# PROC099B_HD_Connector.net
KiCad netlist of a schematic drawn in Altium Designer
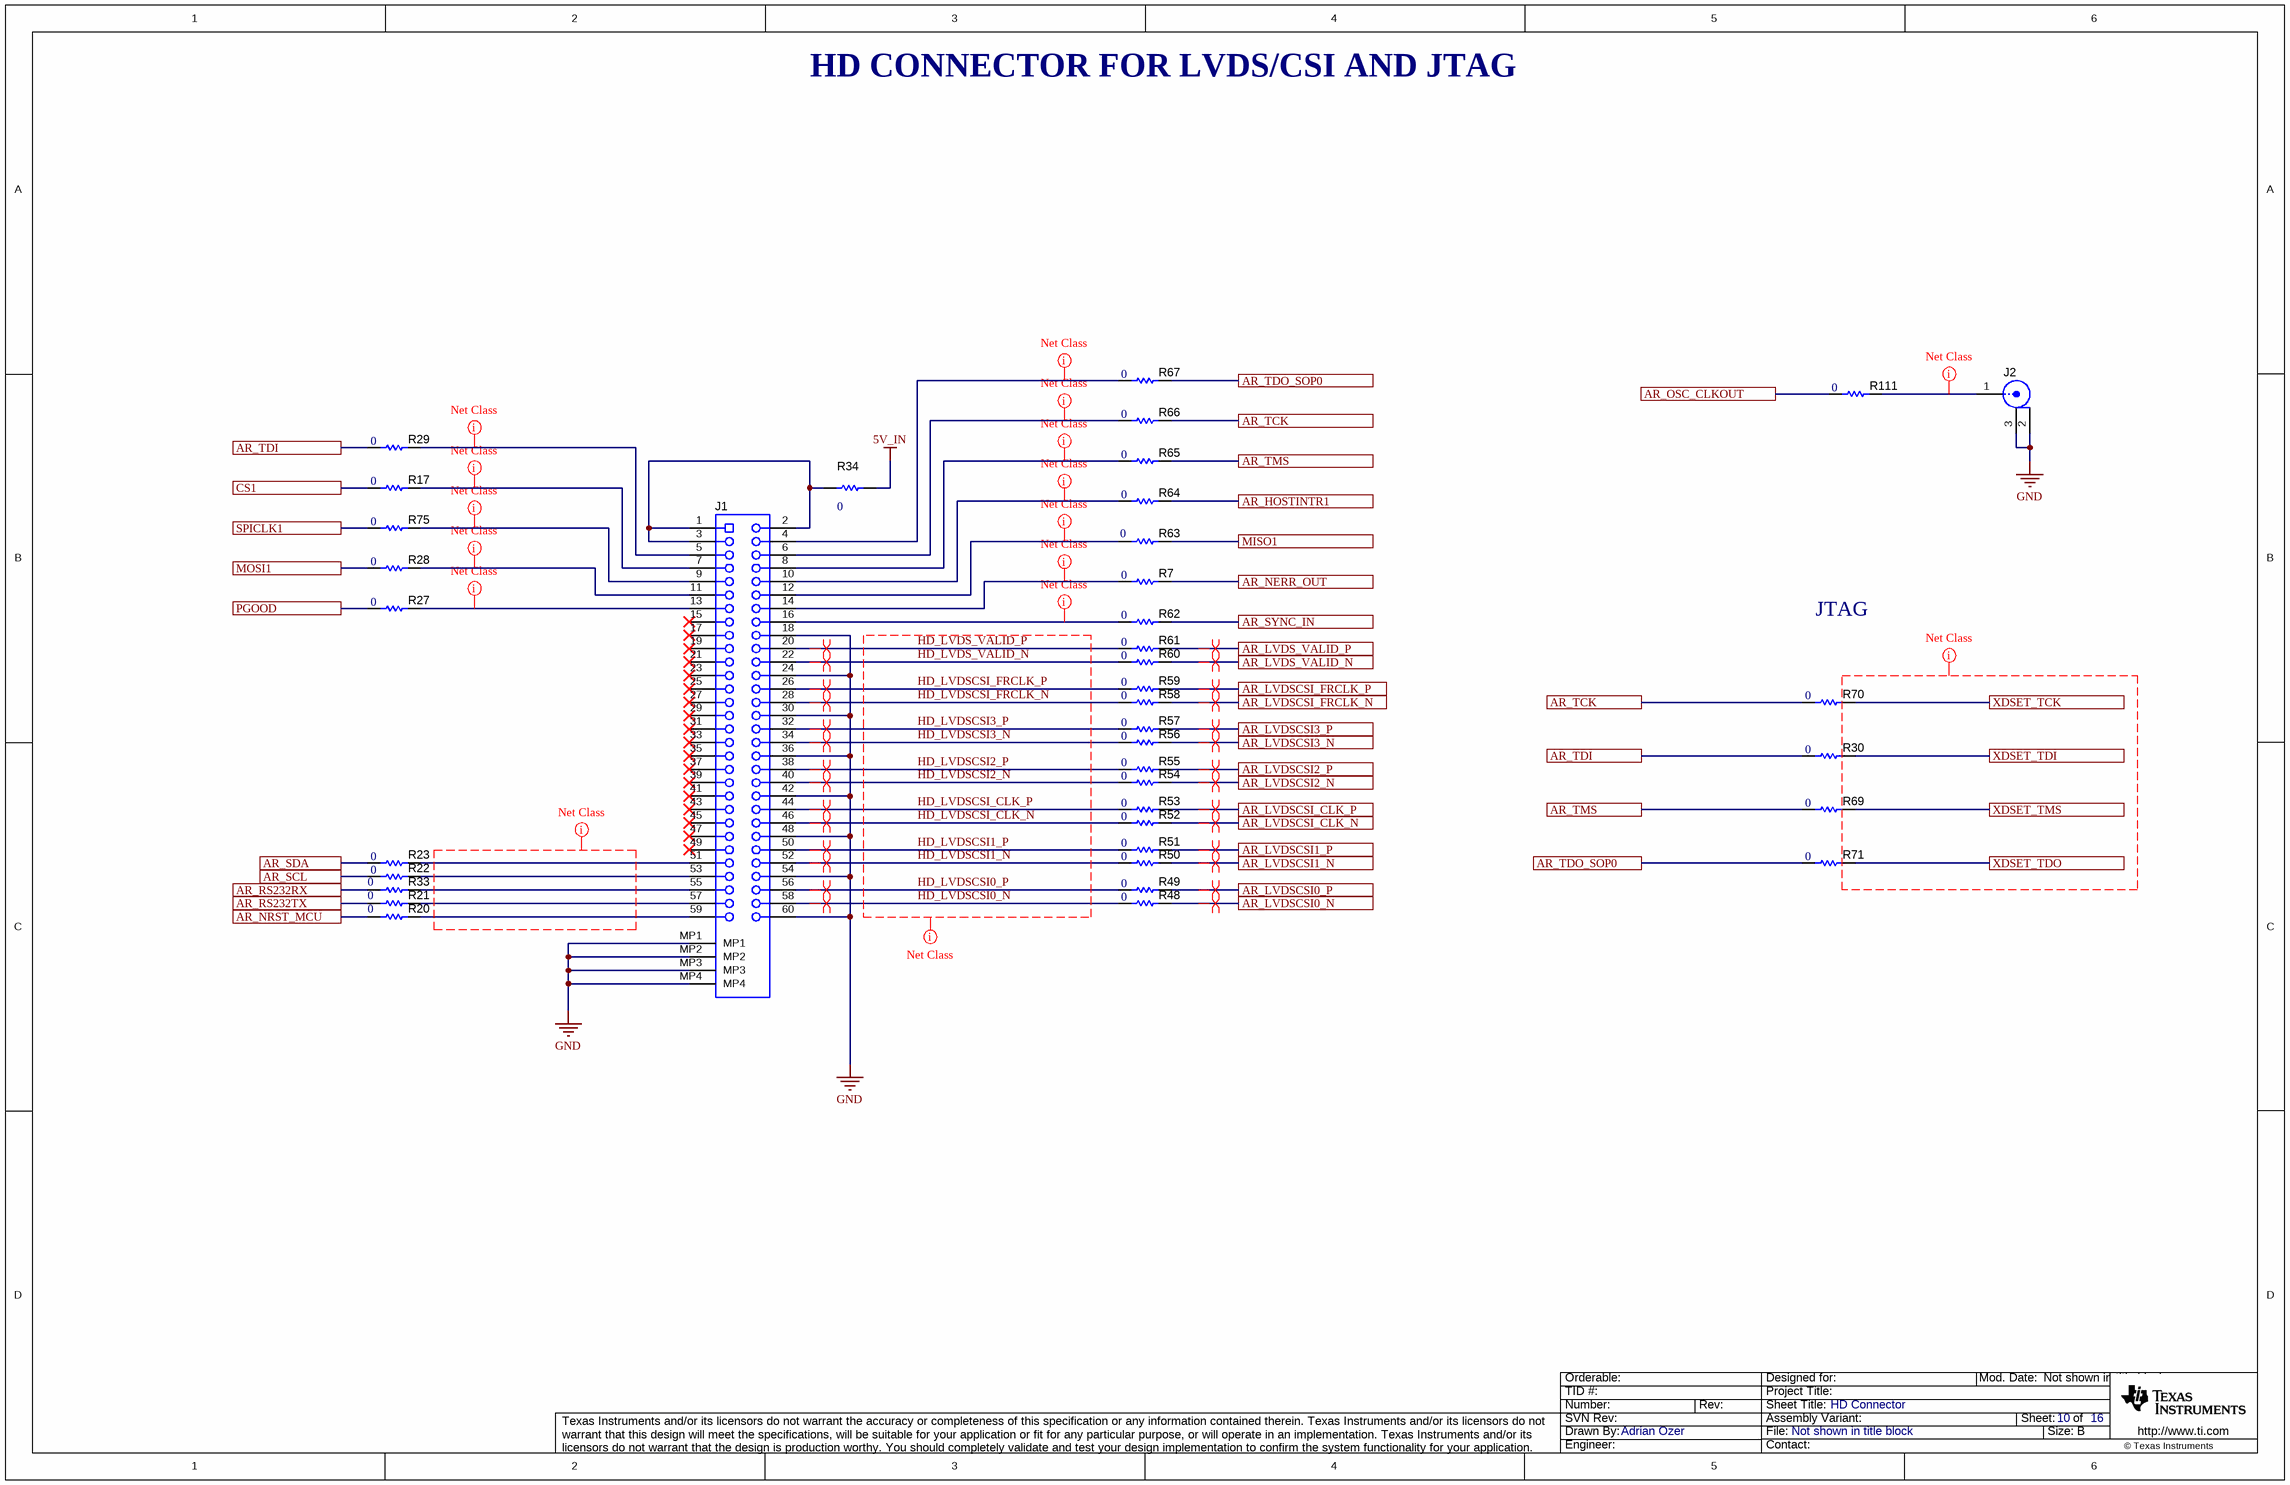
[diagram p0: PROC099B_HD Connector.SchDoc]

(export (version "E")
  (design (tool "Eeschema 10.0.6"))
  (components
    (comp (ref "J1")
      (value "QSH-030-01-L-D-A")
      (footprint "Samtec_QSH-030-01-X-D-A")
      (description "Receptacle, 0.5 mm, 30x2, Gold, TH")
      (fields (field (name "MANUFACTURER") "Samtec") (field (name "PUBLISHER") "Texas Instruments"))
      (libsource (lib "Altium Vault - TI") (part "Receptacle_30x2_4MP_LeftRight"))
    )
    (comp (ref "J2")
      (value "128-0711-201")
      (footprint "Johnson_128-0711-201")
      (description "UMC Straight Jack Receptacle, 50 Ohm, Gold, SMT")
      (fields
        (field (name "MANUFACTURER") "Cinch Connectivity")
        (field (name "PUBLISHER") "Texas Instruments")
      )
      (libsource (lib "Altium Vault - TI") (part "CMP-0055788-1"))
    )
    (comp (ref "R7")
      (value "CRCW02010000Z0ED")
      (footprint "0201_Silk")
      (description "RES, 0, 5%, 0.05 W, 0201")
      (fields (field (name "MANUFACTURER") "Vishay-Dale") (field (name "VALUEDISPLAYED") "0"))
      (libsource (lib "Altium Vault - TI") (part "Resistor"))
    )
    (comp (ref "R17")
      (value "CRCW02010000Z0ED")
      (footprint "0201_Silk")
      (description "RES, 0, 5%, 0.05 W, 0201")
      (fields (field (name "MANUFACTURER") "Vishay-Dale") (field (name "VALUEDISPLAYED") "0"))
      (libsource (lib "Altium Vault - TI") (part "Resistor"))
    )
    (comp (ref "R20")
      (value "CRCW02010000Z0ED")
      (footprint "0201_Silk")
      (description "RES, 0, 5%, 0.05 W, 0201")
      (fields (field (name "MANUFACTURER") "Vishay-Dale") (field (name "VALUEDISPLAYED") "0"))
      (libsource (lib "Altium Vault - TI") (part "Resistor"))
    )
    (comp (ref "R21")
      (value "CRCW02010000Z0ED")
      (footprint "0201_Silk")
      (description "RES, 0, 5%, 0.05 W, 0201")
      (fields (field (name "MANUFACTURER") "Vishay-Dale") (field (name "VALUEDISPLAYED") "0"))
      (libsource (lib "Altium Vault - TI") (part "Resistor"))
    )
    (comp (ref "R22")
      (value "CRCW02010000Z0ED")
      (footprint "0201_Silk")
      (description "RES, 0, 5%, 0.05 W, 0201")
      (fields (field (name "MANUFACTURER") "Vishay-Dale") (field (name "VALUEDISPLAYED") "0"))
      (libsource (lib "Altium Vault - TI") (part "Resistor"))
    )
    (comp (ref "R23")
      (value "CRCW02010000Z0ED")
      (footprint "0201_Silk")
      (description "RES, 0, 5%, 0.05 W, 0201")
      (fields (field (name "MANUFACTURER") "Vishay-Dale") (field (name "VALUEDISPLAYED") "0"))
      (libsource (lib "Altium Vault - TI") (part "Resistor"))
    )
    (comp (ref "R27")
      (value "CRCW02010000Z0ED")
      (footprint "0201_Silk")
      (description "RES, 0, 5%, 0.05 W, 0201")
      (fields (field (name "MANUFACTURER") "Vishay-Dale") (field (name "VALUEDISPLAYED") "0"))
      (libsource (lib "Altium Vault - TI") (part "Resistor"))
    )
    (comp (ref "R28")
      (value "CRCW02010000Z0ED")
      (footprint "0201_Silk")
      (description "RES, 0, 5%, 0.05 W, 0201")
      (fields (field (name "MANUFACTURER") "Vishay-Dale") (field (name "VALUEDISPLAYED") "0"))
      (libsource (lib "Altium Vault - TI") (part "Resistor"))
    )
    (comp (ref "R29")
      (value "CRCW02010000Z0ED")
      (footprint "0201_Silk")
      (description "RES, 0, 5%, 0.05 W, 0201")
      (fields (field (name "MANUFACTURER") "Vishay-Dale") (field (name "VALUEDISPLAYED") "0"))
      (libsource (lib "Altium Vault - TI") (part "Resistor"))
    )
    (comp (ref "R30")
      (value "CRCW02010000Z0ED")
      (footprint "0201_Silk")
      (description "RES, 0, 5%, 0.05 W, 0201")
      (fields (field (name "MANUFACTURER") "Vishay-Dale") (field (name "VALUEDISPLAYED") "0"))
      (libsource (lib "Altium Vault - TI") (part "Resistor"))
    )
    (comp (ref "R33")
      (value "CRCW02010000Z0ED")
      (footprint "0201_Silk")
      (description "RES, 0, 5%, 0.05 W, 0201")
      (fields (field (name "MANUFACTURER") "Vishay-Dale") (field (name "VALUEDISPLAYED") "0"))
      (libsource (lib "Altium Vault - TI") (part "Resistor"))
    )
    (comp (ref "R34")
      (value "CRCW20100000Z0EF")
      (footprint "2010L")
      (description "RES, 0, 5%, 0.75 W, AEC-Q200 Grade 0, 2010")
      (fields (field (name "MANUFACTURER") "Vishay-Dale") (field (name "VALUEDISPLAYED") "0"))
      (libsource (lib "Altium Vault - TI") (part "CMP-0016044-3"))
    )
    (comp (ref "R48")
      (value "CRCW02010000Z0ED")
      (footprint "0201_Silk")
      (description "RES, 0, 5%, 0.05 W, 0201")
      (fields (field (name "MANUFACTURER") "Vishay-Dale") (field (name "VALUEDISPLAYED") "0"))
      (libsource (lib "Altium Vault - TI") (part "Resistor"))
    )
    (comp (ref "R49")
      (value "CRCW02010000Z0ED")
      (footprint "0201_Silk")
      (description "RES, 0, 5%, 0.05 W, 0201")
      (fields (field (name "MANUFACTURER") "Vishay-Dale") (field (name "VALUEDISPLAYED") "0"))
      (libsource (lib "Altium Vault - TI") (part "Resistor"))
    )
    (comp (ref "R50")
      (value "CRCW02010000Z0ED")
      (footprint "0201_Silk")
      (description "RES, 0, 5%, 0.05 W, 0201")
      (fields (field (name "MANUFACTURER") "Vishay-Dale") (field (name "VALUEDISPLAYED") "0"))
      (libsource (lib "Altium Vault - TI") (part "Resistor"))
    )
    (comp (ref "R51")
      (value "CRCW02010000Z0ED")
      (footprint "0201_Silk")
      (description "RES, 0, 5%, 0.05 W, 0201")
      (fields (field (name "MANUFACTURER") "Vishay-Dale") (field (name "VALUEDISPLAYED") "0"))
      (libsource (lib "Altium Vault - TI") (part "Resistor"))
    )
    (comp (ref "R52")
      (value "CRCW02010000Z0ED")
      (footprint "0201_Silk")
      (description "RES, 0, 5%, 0.05 W, 0201")
      (fields (field (name "MANUFACTURER") "Vishay-Dale") (field (name "VALUEDISPLAYED") "0"))
      (libsource (lib "Altium Vault - TI") (part "Resistor"))
    )
    (comp (ref "R53")
      (value "CRCW02010000Z0ED")
      (footprint "0201_Silk")
      (description "RES, 0, 5%, 0.05 W, 0201")
      (fields (field (name "MANUFACTURER") "Vishay-Dale") (field (name "VALUEDISPLAYED") "0"))
      (libsource (lib "Altium Vault - TI") (part "Resistor"))
    )
    (comp (ref "R54")
      (value "CRCW02010000Z0ED")
      (footprint "0201_Silk")
      (description "RES, 0, 5%, 0.05 W, 0201")
      (fields (field (name "MANUFACTURER") "Vishay-Dale") (field (name "VALUEDISPLAYED") "0"))
      (libsource (lib "Altium Vault - TI") (part "Resistor"))
    )
    (comp (ref "R55")
      (value "CRCW02010000Z0ED")
      (footprint "0201_Silk")
      (description "RES, 0, 5%, 0.05 W, 0201")
      (fields (field (name "MANUFACTURER") "Vishay-Dale") (field (name "VALUEDISPLAYED") "0"))
      (libsource (lib "Altium Vault - TI") (part "Resistor"))
    )
    (comp (ref "R56")
      (value "CRCW02010000Z0ED")
      (footprint "0201_Silk")
      (description "RES, 0, 5%, 0.05 W, 0201")
      (fields (field (name "MANUFACTURER") "Vishay-Dale") (field (name "VALUEDISPLAYED") "0"))
      (libsource (lib "Altium Vault - TI") (part "Resistor"))
    )
    (comp (ref "R57")
      (value "CRCW02010000Z0ED")
      (footprint "0201_Silk")
      (description "RES, 0, 5%, 0.05 W, 0201")
      (fields (field (name "MANUFACTURER") "Vishay-Dale") (field (name "VALUEDISPLAYED") "0"))
      (libsource (lib "Altium Vault - TI") (part "Resistor"))
    )
    (comp (ref "R58")
      (value "CRCW02010000Z0ED")
      (footprint "0201_Silk")
      (description "RES, 0, 5%, 0.05 W, 0201")
      (fields (field (name "MANUFACTURER") "Vishay-Dale") (field (name "VALUEDISPLAYED") "0"))
      (libsource (lib "Altium Vault - TI") (part "Resistor"))
    )
    (comp (ref "R59")
      (value "CRCW02010000Z0ED")
      (footprint "0201_Silk")
      (description "RES, 0, 5%, 0.05 W, 0201")
      (fields (field (name "MANUFACTURER") "Vishay-Dale") (field (name "VALUEDISPLAYED") "0"))
      (libsource (lib "Altium Vault - TI") (part "Resistor"))
    )
    (comp (ref "R60")
      (value "CRCW02010000Z0ED")
      (footprint "0201_Silk")
      (description "RES, 0, 5%, 0.05 W, 0201")
      (fields (field (name "MANUFACTURER") "Vishay-Dale") (field (name "VALUEDISPLAYED") "0"))
      (libsource (lib "Altium Vault - TI") (part "Resistor"))
    )
    (comp (ref "R61")
      (value "CRCW02010000Z0ED")
      (footprint "0201_Silk")
      (description "RES, 0, 5%, 0.05 W, 0201")
      (fields (field (name "MANUFACTURER") "Vishay-Dale") (field (name "VALUEDISPLAYED") "0"))
      (libsource (lib "Altium Vault - TI") (part "Resistor"))
    )
    (comp (ref "R62")
      (value "CRCW02010000Z0ED")
      (footprint "0201_Silk")
      (description "RES, 0, 5%, 0.05 W, 0201")
      (fields (field (name "MANUFACTURER") "Vishay-Dale") (field (name "VALUEDISPLAYED") "0"))
      (libsource (lib "Altium Vault - TI") (part "Resistor"))
    )
    (comp (ref "R63")
      (value "CRCW02010000Z0ED")
      (footprint "0201_Silk")
      (description "RES, 0, 5%, 0.05 W, 0201")
      (fields (field (name "MANUFACTURER") "Vishay-Dale") (field (name "VALUEDISPLAYED") "0"))
      (libsource (lib "Altium Vault - TI") (part "Resistor"))
    )
    (comp (ref "R64")
      (value "CRCW02010000Z0ED")
      (footprint "0201_Silk")
      (description "RES, 0, 5%, 0.05 W, 0201")
      (fields (field (name "MANUFACTURER") "Vishay-Dale") (field (name "VALUEDISPLAYED") "0"))
      (libsource (lib "Altium Vault - TI") (part "Resistor"))
    )
    (comp (ref "R65")
      (value "CRCW02010000Z0ED")
      (footprint "0201_Silk")
      (description "RES, 0, 5%, 0.05 W, 0201")
      (fields (field (name "MANUFACTURER") "Vishay-Dale") (field (name "VALUEDISPLAYED") "0"))
      (libsource (lib "Altium Vault - TI") (part "Resistor"))
    )
    (comp (ref "R66")
      (value "CRCW02010000Z0ED")
      (footprint "0201_Silk")
      (description "RES, 0, 5%, 0.05 W, 0201")
      (fields (field (name "MANUFACTURER") "Vishay-Dale") (field (name "VALUEDISPLAYED") "0"))
      (libsource (lib "Altium Vault - TI") (part "Resistor"))
    )
    (comp (ref "R67")
      (value "CRCW02010000Z0ED")
      (footprint "0201_Silk")
      (description "RES, 0, 5%, 0.05 W, 0201")
      (fields (field (name "MANUFACTURER") "Vishay-Dale") (field (name "VALUEDISPLAYED") "0"))
      (libsource (lib "Altium Vault - TI") (part "Resistor"))
    )
    (comp (ref "R69")
      (value "CRCW02010000Z0ED")
      (footprint "0201_Silk")
      (description "RES, 0, 5%, 0.05 W, 0201")
      (fields (field (name "MANUFACTURER") "Vishay-Dale") (field (name "VALUEDISPLAYED") "0"))
      (libsource (lib "Altium Vault - TI") (part "Resistor"))
    )
    (comp (ref "R70")
      (value "CRCW02010000Z0ED")
      (footprint "0201_Silk")
      (description "RES, 0, 5%, 0.05 W, 0201")
      (fields (field (name "MANUFACTURER") "Vishay-Dale") (field (name "VALUEDISPLAYED") "0"))
      (libsource (lib "Altium Vault - TI") (part "Resistor"))
    )
    (comp (ref "R71")
      (value "CRCW02010000Z0ED")
      (footprint "0201_Silk")
      (description "RES, 0, 5%, 0.05 W, 0201")
      (fields (field (name "MANUFACTURER") "Vishay-Dale") (field (name "VALUEDISPLAYED") "0"))
      (libsource (lib "Altium Vault - TI") (part "Resistor"))
    )
    (comp (ref "R75")
      (value "CRCW02010000Z0ED")
      (footprint "0201_Silk")
      (description "RES, 0, 5%, 0.05 W, 0201")
      (fields (field (name "MANUFACTURER") "Vishay-Dale") (field (name "VALUEDISPLAYED") "0"))
      (libsource (lib "Altium Vault - TI") (part "Resistor"))
    )
    (comp (ref "R111")
      (value "CRCW02010000Z0ED")
      (footprint "0201_Silk")
      (description "RES, 0, 5%, 0.05 W, 0201")
      (fields (field (name "MANUFACTURER") "Vishay-Dale") (field (name "VALUEDISPLAYED") "0"))
      (libsource (lib "Altium Vault - TI") (part "Resistor"))
    )
  )
  (nets
    (net (code "1") (name "/AR_HOSTINTR1") (class "Default")
      (node (ref "R64") (pin "2") (pinfunction "2_2") (pintype "passive"))
    )
    (net (code "2") (name "/AR_LVDSCSI0_N") (class "Default")
      (node (ref "R48") (pin "2") (pinfunction "2_2") (pintype "passive"))
    )
    (net (code "3") (name "/AR_LVDSCSI0_P") (class "Default")
      (node (ref "R49") (pin "2") (pinfunction "2_2") (pintype "passive"))
    )
    (net (code "4") (name "/AR_LVDSCSI1_N") (class "Default")
      (node (ref "R50") (pin "2") (pinfunction "2_2") (pintype "passive"))
    )
    (net (code "5") (name "/AR_LVDSCSI1_P") (class "Default")
      (node (ref "R51") (pin "2") (pinfunction "2_2") (pintype "passive"))
    )
    (net (code "6") (name "/AR_LVDSCSI2_N") (class "Default")
      (node (ref "R54") (pin "2") (pinfunction "2_2") (pintype "passive"))
    )
    (net (code "7") (name "/AR_LVDSCSI2_P") (class "Default")
      (node (ref "R55") (pin "2") (pinfunction "2_2") (pintype "passive"))
    )
    (net (code "8") (name "/AR_LVDSCSI3_N") (class "Default")
      (node (ref "R56") (pin "2") (pinfunction "2_2") (pintype "passive"))
    )
    (net (code "9") (name "/AR_LVDSCSI3_P") (class "Default")
      (node (ref "R57") (pin "2") (pinfunction "2_2") (pintype "passive"))
    )
    (net (code "10") (name "/AR_LVDSCSI_CLK_N") (class "Default")
      (node (ref "R52") (pin "2") (pinfunction "2_2") (pintype "passive"))
    )
    (net (code "11") (name "/AR_LVDSCSI_CLK_P") (class "Default")
      (node (ref "R53") (pin "2") (pinfunction "2_2") (pintype "passive"))
    )
    (net (code "12") (name "/AR_LVDSCSI_FRCLK_N") (class "Default")
      (node (ref "R58") (pin "2") (pinfunction "2_2") (pintype "passive"))
    )
    (net (code "13") (name "/AR_LVDSCSI_FRCLK_P") (class "Default")
      (node (ref "R59") (pin "2") (pinfunction "2_2") (pintype "passive"))
    )
    (net (code "14") (name "/AR_LVDS_VALID_N") (class "Default")
      (node (ref "R60") (pin "2") (pinfunction "2_2") (pintype "passive"))
    )
    (net (code "15") (name "/AR_LVDS_VALID_P") (class "Default")
      (node (ref "R61") (pin "2") (pinfunction "2_2") (pintype "passive"))
    )
    (net (code "16") (name "/AR_NERR_OUT") (class "Default")
      (node (ref "R7") (pin "2") (pinfunction "2_2") (pintype "passive"))
    )
    (net (code "17") (name "/AR_NRST_MCU") (class "Default")
      (node (ref "R20") (pin "1") (pinfunction "1_1") (pintype "passive"))
    )
    (net (code "18") (name "/AR_OSC_CLKOUT") (class "Default")
      (node (ref "R111") (pin "1") (pinfunction "1_1") (pintype "passive"))
    )
    (net (code "19") (name "/AR_RS232RX") (class "Default")
      (node (ref "R33") (pin "1") (pinfunction "1_1") (pintype "passive"))
    )
    (net (code "20") (name "/AR_RS232TX") (class "Default")
      (node (ref "R21") (pin "1") (pinfunction "1_1") (pintype "passive"))
    )
    (net (code "21") (name "/AR_SCL") (class "Default")
      (node (ref "R22") (pin "1") (pinfunction "1_1") (pintype "passive"))
    )
    (net (code "22") (name "/AR_SDA") (class "Default")
      (node (ref "R23") (pin "1") (pinfunction "1_1") (pintype "passive"))
    )
    (net (code "23") (name "/AR_SYNC_IN") (class "Default")
      (node (ref "R62") (pin "2") (pinfunction "2_2") (pintype "passive"))
    )
    (net (code "24") (name "/AR_TCK") (class "Default")
      (node (ref "R66") (pin "2") (pinfunction "2_2") (pintype "passive"))
      (node (ref "R70") (pin "1") (pinfunction "1_1") (pintype "passive"))
    )
    (net (code "25") (name "/AR_TDI") (class "Default")
      (node (ref "R29") (pin "1") (pinfunction "1_1") (pintype "passive"))
      (node (ref "R30") (pin "1") (pinfunction "1_1") (pintype "passive"))
    )
    (net (code "26") (name "/AR_TDO_SOP0") (class "Default")
      (node (ref "R67") (pin "2") (pinfunction "2_2") (pintype "passive"))
      (node (ref "R71") (pin "1") (pinfunction "1_1") (pintype "passive"))
    )
    (net (code "27") (name "/AR_TMS") (class "Default")
      (node (ref "R65") (pin "2") (pinfunction "2_2") (pintype "passive"))
      (node (ref "R69") (pin "1") (pinfunction "1_1") (pintype "passive"))
    )
    (net (code "28") (name "/CS1") (class "Default")
      (node (ref "R17") (pin "1") (pinfunction "1_1") (pintype "passive"))
    )
    (net (code "29") (name "/HD_LVDSCSI0_N") (class "Default")
      (node (ref "J1") (pin "58") (pinfunction "58_58") (pintype "passive"))
      (node (ref "R48") (pin "1") (pinfunction "1_1") (pintype "passive"))
    )
    (net (code "30") (name "/HD_LVDSCSI0_P") (class "Default")
      (node (ref "J1") (pin "56") (pinfunction "56_56") (pintype "passive"))
      (node (ref "R49") (pin "1") (pinfunction "1_1") (pintype "passive"))
    )
    (net (code "31") (name "/HD_LVDSCSI1_N") (class "Default")
      (node (ref "J1") (pin "52") (pinfunction "52_52") (pintype "passive"))
      (node (ref "R50") (pin "1") (pinfunction "1_1") (pintype "passive"))
    )
    (net (code "32") (name "/HD_LVDSCSI1_P") (class "Default")
      (node (ref "J1") (pin "50") (pinfunction "50_50") (pintype "passive"))
      (node (ref "R51") (pin "1") (pinfunction "1_1") (pintype "passive"))
    )
    (net (code "33") (name "/HD_LVDSCSI2_N") (class "Default")
      (node (ref "J1") (pin "40") (pinfunction "40_40") (pintype "passive"))
      (node (ref "R54") (pin "1") (pinfunction "1_1") (pintype "passive"))
    )
    (net (code "34") (name "/HD_LVDSCSI2_P") (class "Default")
      (node (ref "J1") (pin "38") (pinfunction "38_38") (pintype "passive"))
      (node (ref "R55") (pin "1") (pinfunction "1_1") (pintype "passive"))
    )
    (net (code "35") (name "/HD_LVDSCSI3_N") (class "Default")
      (node (ref "J1") (pin "34") (pinfunction "34_34") (pintype "passive"))
      (node (ref "R56") (pin "1") (pinfunction "1_1") (pintype "passive"))
    )
    (net (code "36") (name "/HD_LVDSCSI3_P") (class "Default")
      (node (ref "J1") (pin "32") (pinfunction "32_32") (pintype "passive"))
      (node (ref "R57") (pin "1") (pinfunction "1_1") (pintype "passive"))
    )
    (net (code "37") (name "/HD_LVDSCSI_CLK_N") (class "Default")
      (node (ref "J1") (pin "46") (pinfunction "46_46") (pintype "passive"))
      (node (ref "R52") (pin "1") (pinfunction "1_1") (pintype "passive"))
    )
    (net (code "38") (name "/HD_LVDSCSI_CLK_P") (class "Default")
      (node (ref "J1") (pin "44") (pinfunction "44_44") (pintype "passive"))
      (node (ref "R53") (pin "1") (pinfunction "1_1") (pintype "passive"))
    )
    (net (code "39") (name "/HD_LVDSCSI_FRCLK_N") (class "Default")
      (node (ref "J1") (pin "28") (pinfunction "28_28") (pintype "passive"))
      (node (ref "R58") (pin "1") (pinfunction "1_1") (pintype "passive"))
    )
    (net (code "40") (name "/HD_LVDSCSI_FRCLK_P") (class "Default")
      (node (ref "J1") (pin "26") (pinfunction "26_26") (pintype "passive"))
      (node (ref "R59") (pin "1") (pinfunction "1_1") (pintype "passive"))
    )
    (net (code "41") (name "/HD_LVDS_VALID_N") (class "Default")
      (node (ref "J1") (pin "22") (pinfunction "22_22") (pintype "passive"))
      (node (ref "R60") (pin "1") (pinfunction "1_1") (pintype "passive"))
    )
    (net (code "42") (name "/HD_LVDS_VALID_P") (class "Default")
      (node (ref "J1") (pin "20") (pinfunction "20_20") (pintype "passive"))
      (node (ref "R61") (pin "1") (pinfunction "1_1") (pintype "passive"))
    )
    (net (code "43") (name "/MISO1") (class "Default")
      (node (ref "R63") (pin "2") (pinfunction "2_2") (pintype "passive"))
    )
    (net (code "44") (name "/MOSI1") (class "Default")
      (node (ref "R28") (pin "1") (pinfunction "1_1") (pintype "passive"))
    )
    (net (code "45") (name "/PGOOD") (class "Default")
      (node (ref "R27") (pin "1") (pinfunction "1_1") (pintype "passive"))
    )
    (net (code "46") (name "/SPICLK1") (class "Default")
      (node (ref "R75") (pin "1") (pinfunction "1_1") (pintype "passive"))
    )
    (net (code "47") (name "/XDSET_TCK") (class "Default")
      (node (ref "R70") (pin "2") (pinfunction "2_2") (pintype "passive"))
    )
    (net (code "48") (name "/XDSET_TDI") (class "Default")
      (node (ref "R30") (pin "2") (pinfunction "2_2") (pintype "passive"))
    )
    (net (code "49") (name "/XDSET_TDO") (class "Default")
      (node (ref "R71") (pin "2") (pinfunction "2_2") (pintype "passive"))
    )
    (net (code "50") (name "/XDSET_TMS") (class "Default")
      (node (ref "R69") (pin "2") (pinfunction "2_2") (pintype "passive"))
    )
    (net (code "51") (name "5V_IN") (class "Default")
      (node (ref "R34") (pin "2") (pinfunction "2_2") (pintype "passive"))
    )
    (net (code "52") (name "GND") (class "Default")
      (node (ref "J1") (pin "18") (pinfunction "18_18") (pintype "passive"))
      (node (ref "J1") (pin "24") (pinfunction "24_24") (pintype "passive"))
      (node (ref "J1") (pin "30") (pinfunction "30_30") (pintype "passive"))
      (node (ref "J1") (pin "36") (pinfunction "36_36") (pintype "passive"))
      (node (ref "J1") (pin "42") (pinfunction "42_42") (pintype "passive"))
      (node (ref "J1") (pin "48") (pinfunction "48_48") (pintype "passive"))
      (node (ref "J1") (pin "54") (pinfunction "54_54") (pintype "passive"))
      (node (ref "J1") (pin "60") (pinfunction "60_60") (pintype "passive"))
      (node (ref "J1") (pin "MP1") (pinfunction "MP1_MP1") (pintype "passive"))
      (node (ref "J1") (pin "MP2") (pinfunction "MP2_MP2") (pintype "passive"))
      (node (ref "J1") (pin "MP3") (pinfunction "MP3_MP3") (pintype "passive"))
      (node (ref "J1") (pin "MP4") (pinfunction "MP4_MP4") (pintype "passive"))
      (node (ref "J2") (pin "2") (pinfunction "2_2") (pintype "passive"))
      (node (ref "J2") (pin "3") (pinfunction "3_3") (pintype "passive"))
    )
    (net (code "53") (name "Net-(J1-Pad1)") (class "Default")
      (node (ref "J1") (pin "1") (pinfunction "1_1") (pintype "passive"))
      (node (ref "J1") (pin "2") (pinfunction "2_2") (pintype "passive"))
      (node (ref "J1") (pin "3") (pinfunction "3_3") (pintype "passive"))
      (node (ref "R34") (pin "1") (pinfunction "1_1") (pintype "passive"))
    )
    (net (code "54") (name "Net-(J1-Pad4)") (class "Default")
      (node (ref "J1") (pin "4") (pinfunction "4_4") (pintype "passive"))
      (node (ref "R67") (pin "1") (pinfunction "1_1") (pintype "passive"))
    )
    (net (code "55") (name "Net-(J1-Pad5)") (class "Default")
      (node (ref "J1") (pin "5") (pinfunction "5_5") (pintype "passive"))
      (node (ref "R29") (pin "2") (pinfunction "2_2") (pintype "passive"))
    )
    (net (code "56") (name "Net-(J1-Pad6)") (class "Default")
      (node (ref "J1") (pin "6") (pinfunction "6_6") (pintype "passive"))
      (node (ref "R66") (pin "1") (pinfunction "1_1") (pintype "passive"))
    )
    (net (code "57") (name "Net-(J1-Pad7)") (class "Default")
      (node (ref "J1") (pin "7") (pinfunction "7_7") (pintype "passive"))
      (node (ref "R17") (pin "2") (pinfunction "2_2") (pintype "passive"))
    )
    (net (code "58") (name "Net-(J1-Pad8)") (class "Default")
      (node (ref "J1") (pin "8") (pinfunction "8_8") (pintype "passive"))
      (node (ref "R65") (pin "1") (pinfunction "1_1") (pintype "passive"))
    )
    (net (code "59") (name "Net-(J1-Pad9)") (class "Default")
      (node (ref "J1") (pin "9") (pinfunction "9_9") (pintype "passive"))
      (node (ref "R75") (pin "2") (pinfunction "2_2") (pintype "passive"))
    )
    (net (code "60") (name "Net-(J1-Pad10)") (class "Default")
      (node (ref "J1") (pin "10") (pinfunction "10_10") (pintype "passive"))
      (node (ref "R64") (pin "1") (pinfunction "1_1") (pintype "passive"))
    )
    (net (code "61") (name "Net-(J1-Pad11)") (class "Default")
      (node (ref "J1") (pin "11") (pinfunction "11_11") (pintype "passive"))
      (node (ref "R28") (pin "2") (pinfunction "2_2") (pintype "passive"))
    )
    (net (code "62") (name "Net-(J1-Pad12)") (class "Default")
      (node (ref "J1") (pin "12") (pinfunction "12_12") (pintype "passive"))
      (node (ref "R63") (pin "1") (pinfunction "1_1") (pintype "passive"))
    )
    (net (code "63") (name "Net-(J1-Pad13)") (class "Default")
      (node (ref "J1") (pin "13") (pinfunction "13_13") (pintype "passive"))
      (node (ref "R27") (pin "2") (pinfunction "2_2") (pintype "passive"))
    )
    (net (code "64") (name "Net-(J1-Pad14)") (class "Default")
      (node (ref "J1") (pin "14") (pinfunction "14_14") (pintype "passive"))
      (node (ref "R7") (pin "1") (pinfunction "1_1") (pintype "passive"))
    )
    (net (code "65") (name "Net-(J1-Pad16)") (class "Default")
      (node (ref "J1") (pin "16") (pinfunction "16_16") (pintype "passive"))
      (node (ref "R62") (pin "1") (pinfunction "1_1") (pintype "passive"))
    )
    (net (code "66") (name "Net-(J1-Pad51)") (class "Default")
      (node (ref "J1") (pin "51") (pinfunction "51_51") (pintype "passive"))
      (node (ref "R23") (pin "2") (pinfunction "2_2") (pintype "passive"))
    )
    (net (code "67") (name "Net-(J1-Pad53)") (class "Default")
      (node (ref "J1") (pin "53") (pinfunction "53_53") (pintype "passive"))
      (node (ref "R22") (pin "2") (pinfunction "2_2") (pintype "passive"))
    )
    (net (code "68") (name "Net-(J1-Pad55)") (class "Default")
      (node (ref "J1") (pin "55") (pinfunction "55_55") (pintype "passive"))
      (node (ref "R33") (pin "2") (pinfunction "2_2") (pintype "passive"))
    )
    (net (code "69") (name "Net-(J1-Pad57)") (class "Default")
      (node (ref "J1") (pin "57") (pinfunction "57_57") (pintype "passive"))
      (node (ref "R21") (pin "2") (pinfunction "2_2") (pintype "passive"))
    )
    (net (code "70") (name "Net-(J1-Pad59)") (class "Default")
      (node (ref "J1") (pin "59") (pinfunction "59_59") (pintype "passive"))
      (node (ref "R20") (pin "2") (pinfunction "2_2") (pintype "passive"))
    )
    (net (code "71") (name "Net-(J2-Pad1)") (class "Default")
      (node (ref "J2") (pin "1") (pinfunction "1_1") (pintype "passive"))
      (node (ref "R111") (pin "2") (pinfunction "2_2") (pintype "passive"))
    )
    (net (code "72") (name "unconnected-(J1-Pad15)") (class "Default")
      (node (ref "J1") (pin "15") (pinfunction "15_15") (pintype "passive+no_connect"))
    )
    (net (code "73") (name "unconnected-(J1-Pad17)") (class "Default")
      (node (ref "J1") (pin "17") (pinfunction "17_17") (pintype "passive+no_connect"))
    )
    (net (code "74") (name "unconnected-(J1-Pad19)") (class "Default")
      (node (ref "J1") (pin "19") (pinfunction "19_19") (pintype "passive+no_connect"))
    )
    (net (code "75") (name "unconnected-(J1-Pad21)") (class "Default")
      (node (ref "J1") (pin "21") (pinfunction "21_21") (pintype "passive+no_connect"))
    )
    (net (code "76") (name "unconnected-(J1-Pad23)") (class "Default")
      (node (ref "J1") (pin "23") (pinfunction "23_23") (pintype "passive+no_connect"))
    )
    (net (code "77") (name "unconnected-(J1-Pad25)") (class "Default")
      (node (ref "J1") (pin "25") (pinfunction "25_25") (pintype "passive+no_connect"))
    )
    (net (code "78") (name "unconnected-(J1-Pad27)") (class "Default")
      (node (ref "J1") (pin "27") (pinfunction "27_27") (pintype "passive+no_connect"))
    )
    (net (code "79") (name "unconnected-(J1-Pad29)") (class "Default")
      (node (ref "J1") (pin "29") (pinfunction "29_29") (pintype "passive+no_connect"))
    )
    (net (code "80") (name "unconnected-(J1-Pad31)") (class "Default")
      (node (ref "J1") (pin "31") (pinfunction "31_31") (pintype "passive+no_connect"))
    )
    (net (code "81") (name "unconnected-(J1-Pad33)") (class "Default")
      (node (ref "J1") (pin "33") (pinfunction "33_33") (pintype "passive+no_connect"))
    )
    (net (code "82") (name "unconnected-(J1-Pad35)") (class "Default")
      (node (ref "J1") (pin "35") (pinfunction "35_35") (pintype "passive+no_connect"))
    )
    (net (code "83") (name "unconnected-(J1-Pad37)") (class "Default")
      (node (ref "J1") (pin "37") (pinfunction "37_37") (pintype "passive+no_connect"))
    )
    (net (code "84") (name "unconnected-(J1-Pad39)") (class "Default")
      (node (ref "J1") (pin "39") (pinfunction "39_39") (pintype "passive+no_connect"))
    )
    (net (code "85") (name "unconnected-(J1-Pad41)") (class "Default")
      (node (ref "J1") (pin "41") (pinfunction "41_41") (pintype "passive+no_connect"))
    )
    (net (code "86") (name "unconnected-(J1-Pad43)") (class "Default")
      (node (ref "J1") (pin "43") (pinfunction "43_43") (pintype "passive+no_connect"))
    )
    (net (code "87") (name "unconnected-(J1-Pad45)") (class "Default")
      (node (ref "J1") (pin "45") (pinfunction "45_45") (pintype "passive+no_connect"))
    )
    (net (code "88") (name "unconnected-(J1-Pad47)") (class "Default")
      (node (ref "J1") (pin "47") (pinfunction "47_47") (pintype "passive+no_connect"))
    )
    (net (code "89") (name "unconnected-(J1-Pad49)") (class "Default")
      (node (ref "J1") (pin "49") (pinfunction "49_49") (pintype "passive+no_connect"))
    )
  )
)
